# zulu_a7_4.net
KiCad netlist of a schematic drawn in Altium Designer
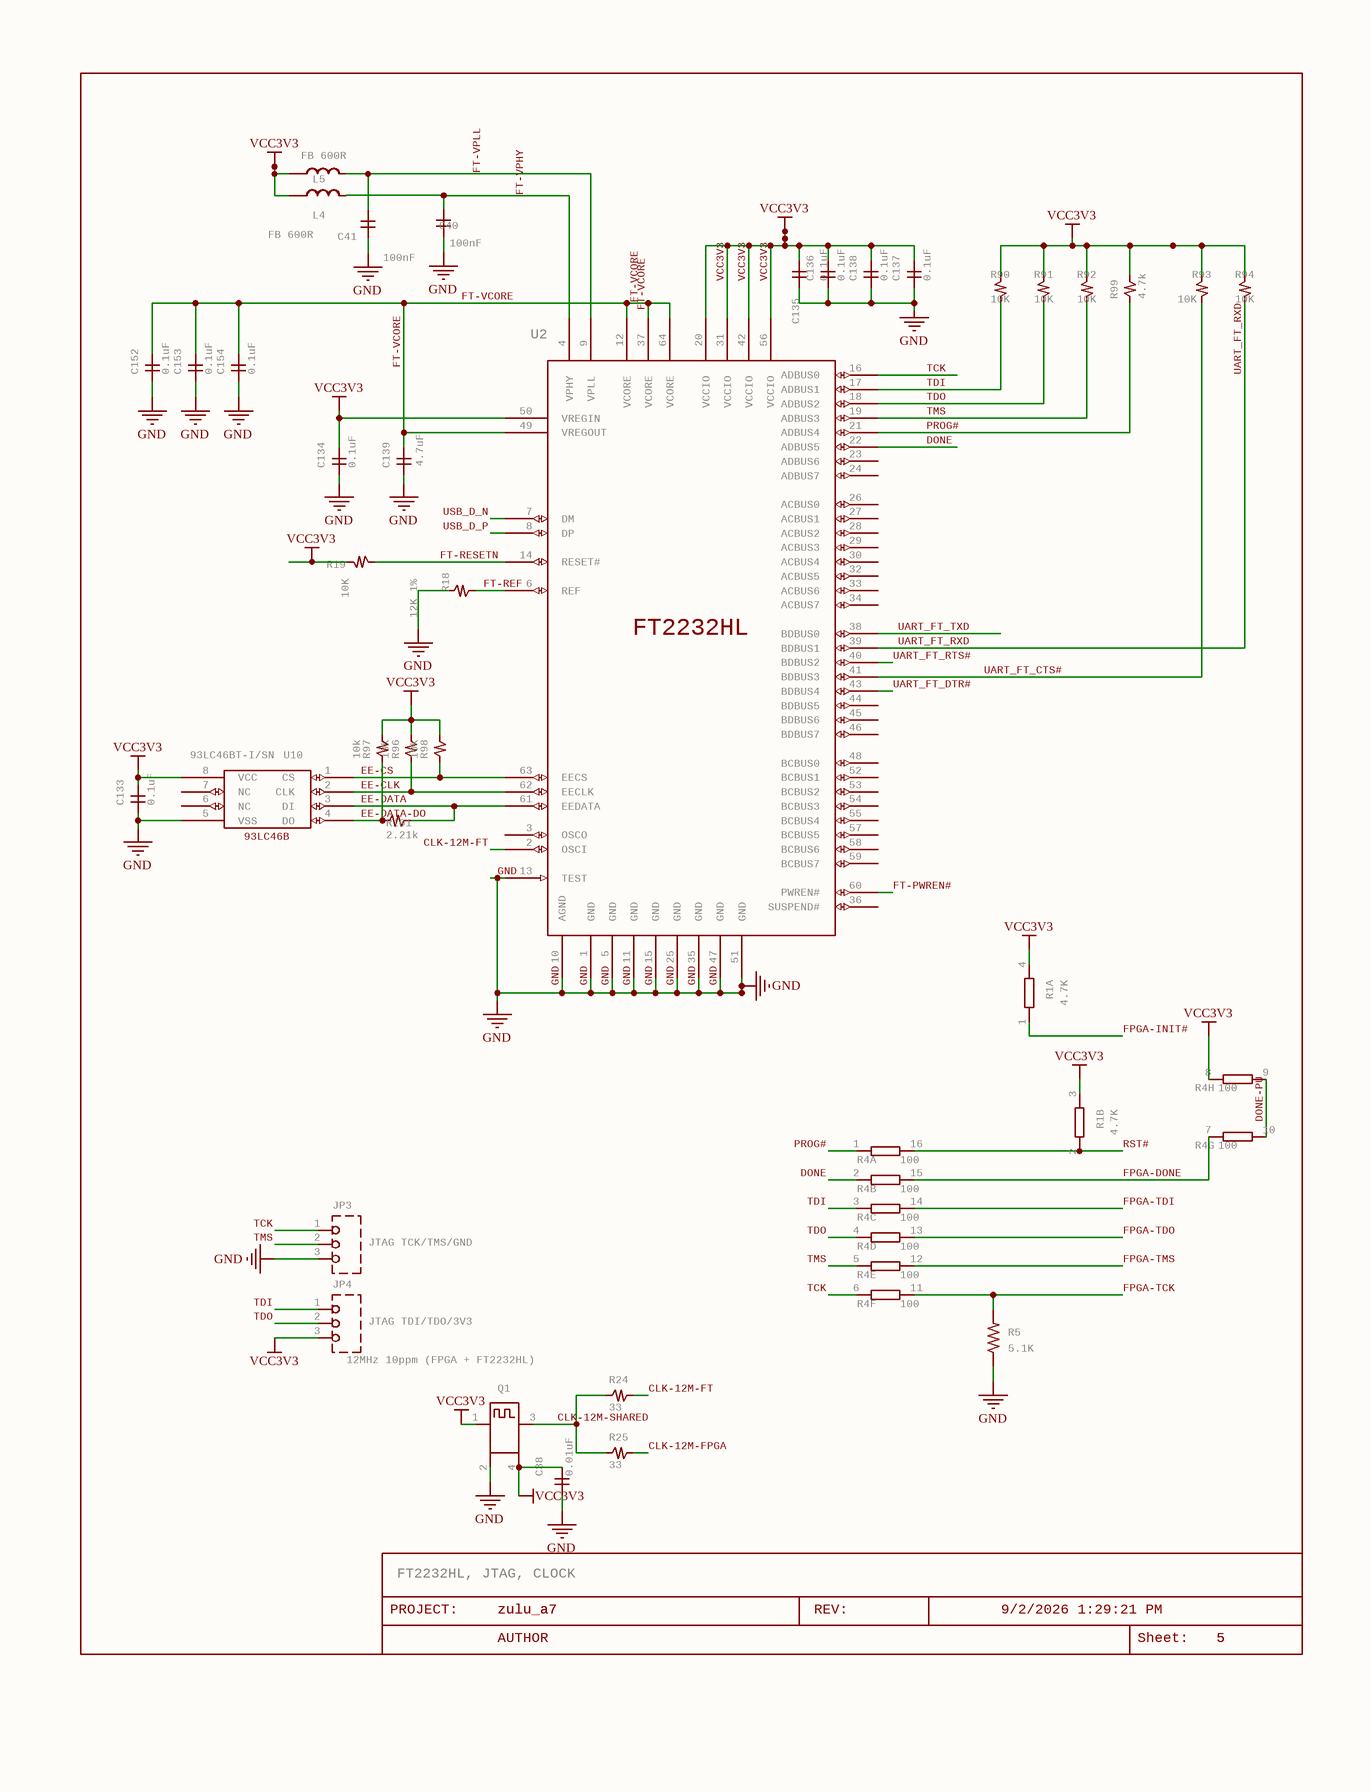
[diagram p0: zulu_a7_4.SchDoc]

(export (version "E")
  (design (tool "Eeschema 10.0.6"))
  (components
    (comp (ref "C38")
      (value "0.01uF")
      (footprint "C0201")
      (description "CAPACITOR, generic non-polarized, horizontal pins")
      (fields (field (name "MANF") "Murata"))
      (libsource (lib "rcl") (part "C-GENERICC0201"))
    )
    (comp (ref "C40")
      (value "100nF")
      (footprint "C0201")
      (description "CAPACITOR, generic non-polarized, horizontal pins")
      (fields (field (name "MANF") "Murata"))
      (libsource (lib "rcl") (part "C-GENERICC0201"))
    )
    (comp (ref "C41")
      (value "100nF")
      (footprint "C0201")
      (description "CAPACITOR, generic non-polarized, horizontal pins")
      (fields (field (name "MANF") "Murata"))
      (libsource (lib "") (part "C-GENERICC0201_2"))
    )
    (comp (ref "C133")
      (value "0.1uF")
      (footprint "C0201")
      (description "CAPACITOR, generic non-polarized, horizontal pins")
      (fields (field (name "MANF") "Murata"))
      (libsource (lib "rcl") (part "C-GENERICC0201"))
    )
    (comp (ref "C134")
      (value "0.1uF")
      (footprint "C0201")
      (description "CAPACITOR, generic non-polarized, horizontal pins")
      (fields (field (name "MANF") "Murata"))
      (libsource (lib "rcl") (part "C-GENERICC0201"))
    )
    (comp (ref "C135")
      (value "0.1uF")
      (footprint "C0201")
      (description "CAPACITOR, generic non-polarized, horizontal pins")
      (fields (field (name "MANF") "Murata"))
      (libsource (lib "rcl") (part "C-GENERICC0201"))
    )
    (comp (ref "C136")
      (value "0.1uF")
      (footprint "C0201")
      (description "CAPACITOR, generic non-polarized, horizontal pins")
      (fields (field (name "MANF") "Murata"))
      (libsource (lib "rcl") (part "C-GENERICC0201"))
    )
    (comp (ref "C137")
      (value "0.1uF")
      (footprint "C0201")
      (description "CAPACITOR, generic non-polarized, horizontal pins")
      (fields (field (name "MANF") "Murata"))
      (libsource (lib "rcl") (part "C-GENERICC0201"))
    )
    (comp (ref "C138")
      (value "0.1uF")
      (footprint "C0201")
      (description "CAPACITOR, generic non-polarized, horizontal pins")
      (fields (field (name "MANF") "Murata"))
      (libsource (lib "rcl") (part "C-GENERICC0201"))
    )
    (comp (ref "C139")
      (value "4.7uF")
      (footprint "C0402")
      (description "CAPACITOR, generic non-polarized, horizontal pins")
      (fields (field (name "MANF") "Taiyo Yuden"))
      (libsource (lib "rcl") (part "C-GENERICC0402"))
    )
    (comp (ref "C152")
      (value "0.1uF")
      (footprint "C0201")
      (description "CAPACITOR, generic non-polarized, horizontal pins")
      (fields (field (name "MANF") "Murata"))
      (libsource (lib "") (part "C-GENERICC0201_1"))
    )
    (comp (ref "C153")
      (value "0.1uF")
      (footprint "C0201")
      (description "CAPACITOR, generic non-polarized, horizontal pins")
      (fields (field (name "MANF") "Murata"))
      (libsource (lib "") (part "C-GENERICC0201_1"))
    )
    (comp (ref "C154")
      (value "0.1uF")
      (footprint "C0201")
      (description "CAPACITOR, generic non-polarized, horizontal pins")
      (fields (field (name "MANF") "Murata"))
      (libsource (lib "") (part "C-GENERICC0201_1"))
    )
    (comp (ref "FRAME4")
      (value "DOCFIELD")
      (description "DOCUMENT FIELD")
      (fields
        (field (name "LAST_DATE_TIME") "9/2/2026 1:29:21 PM")
        (field (name "SHEET") "Sheet:")
        (field (name "SHEET_1") "5")
        (field (name "REV") "REV:")
        (field (name "PROJECT") "PROJECT:")
        (field (name "DRAWING_NAME") "zulu_a7")
        (field (name "AUTHOR") "AUTHOR")
        (field (name "DRAWING_NAME_1") "zulu_a7")
        (field (name "SHEET_2") "5")
        (field (name "LIBRARYNAME") "ctambe")
      )
      (libsource (lib "ctambe") (part "DOCFIELD"))
    )
    (comp (ref "JP3")
      (value "JTAG TCK/TMS/GND")
      (footprint "1X03-NOSILK")
      (fields (field (name "LIBRARYNAME") "pinhead"))
      (libsource (lib "pinhead") (part "TESTPT-1X3NOSILK"))
    )
    (comp (ref "JP4")
      (value "JTAG TDI/TDO/3V3")
      (footprint "1X03-NOSILK")
      (fields (field (name "LIBRARYNAME") "pinhead"))
      (libsource (lib "pinhead") (part "TESTPT-1X3NOSILK"))
    )
    (comp (ref "L4")
      (value "FB 600R")
      (footprint "IND0603")
      (description "INDUCTOR, generic power inductor")
      (fields (field (name "MANF") "Murata") (field (name "LIBRARYNAME") "ctambe"))
      (libsource (lib "ctambe") (part "INDUCTOR"))
    )
    (comp (ref "L5")
      (value "FB 600R")
      (footprint "IND0603")
      (description "INDUCTOR, generic power inductor")
      (fields (field (name "MANF") "Murata") (field (name "LIBRARYNAME") "ctambe"))
      (libsource (lib "ctambe") (part "INDUCTOR"))
    )
    (comp (ref "Q1")
      (value "12MHz 10ppm (FPGA + FT2232HL)")
      (footprint "32X25")
      (description "Crystal Chip")
      (fields (field (name "MANF") "ECS") (field (name "LIBRARYNAME") "ctambe"))
      (libsource (lib "ctambe") (part "OSC_CHIPASEM1-12MHZ"))
    )
    (comp (ref "R1")
      (value "4.7K")
      (footprint "742C043")
      (description "Resistor 2-pack   Package of two resistors.")
      (fields (field (name "MANF") "CTS") (field (name "LIBRARYNAME") "ctambe"))
      (libsource (lib "") (part "RES2742_1"))
    )
    (comp (ref "R4")
      (value "100")
      (footprint "742C163")
      (description "Resistor 8-pack   Package of eight resistors, six used.")
      (fields (field (name "MANF") "CTS") (field (name "LIBRARYNAME") "ctambe"))
      (libsource (lib "ctambe") (part "RES8742"))
    )
    (comp (ref "R5")
      (value "5.1K")
      (footprint "R0201")
      (description "RESISTOR, American symbol")
      (fields (field (name "MANF") "Yageo"))
      (libsource (lib "rcl") (part "R-US_R0201"))
    )
    (comp (ref "R18")
      (value "12K 1%")
      (footprint "R0402")
      (description "RESISTOR, American symbol, small 2-zigzag variant (sheet 2 only)")
      (fields (field (name "MANF") "Yageo"))
      (libsource (lib "rcl") (part "R-US_SMALLR0402"))
    )
    (comp (ref "R19")
      (value "10K")
      (footprint "R0201")
      (description "RESISTOR, American symbol, small 2-zigzag variant (sheet 2 only)")
      (fields (field (name "MANF") "Yageo"))
      (libsource (lib "rcl") (part "R-US_SMALLR0201"))
    )
    (comp (ref "R24")
      (value "33")
      (footprint "R0201")
      (description "RESISTOR, American symbol, small 2-zigzag variant (sheet 2 only)")
      (fields (field (name "MANF") "Yageo"))
      (libsource (lib "rcl") (part "R-US_SMALLR0201"))
    )
    (comp (ref "R25")
      (value "33")
      (footprint "R0201")
      (description "RESISTOR, American symbol, small 2-zigzag variant (sheet 2 only)")
      (fields (field (name "MANF") "Yageo"))
      (libsource (lib "rcl") (part "R-US_SMALLR0201"))
    )
    (comp (ref "R90")
      (value "10K")
      (footprint "R0201")
      (description "RESISTOR, American symbol, small 2-zigzag variant (sheet 2 only)")
      (fields (field (name "MANF") "Yageo"))
      (libsource (lib "rcl") (part "R-US_SMALLR0201"))
    )
    (comp (ref "R91")
      (value "10K")
      (footprint "R0201")
      (description "RESISTOR, American symbol, small 2-zigzag variant (sheet 2 only)")
      (fields (field (name "MANF") "Yageo"))
      (libsource (lib "rcl") (part "R-US_SMALLR0201"))
    )
    (comp (ref "R92")
      (value "10K")
      (footprint "R0201")
      (description "RESISTOR, American symbol, small 2-zigzag variant (sheet 2 only)")
      (fields (field (name "MANF") "Yageo"))
      (libsource (lib "rcl") (part "R-US_SMALLR0201"))
    )
    (comp (ref "R93")
      (value "10K")
      (footprint "R0201")
      (description "RESISTOR, American symbol, small 2-zigzag variant (sheet 2 only)")
      (fields (field (name "MANF") "Yageo"))
      (libsource (lib "rcl") (part "R-US_SMALLR0201"))
    )
    (comp (ref "R94")
      (value "10K")
      (footprint "R0201")
      (description "RESISTOR, American symbol, small 2-zigzag variant (sheet 2 only)")
      (fields (field (name "MANF") "Yageo"))
      (libsource (lib "rcl") (part "R-US_SMALLR0201"))
    )
    (comp (ref "R96")
      (value "10k")
      (footprint "R0201")
      (description "RESISTOR, American symbol, small 2-zigzag variant (sheet 2 only)")
      (fields (field (name "MANF") "Yageo"))
      (libsource (lib "rcl") (part "R-US_SMALLR0201"))
    )
    (comp (ref "R97")
      (value "10k")
      (footprint "R0201")
      (description "RESISTOR, American symbol, small 2-zigzag variant (sheet 2 only)")
      (fields (field (name "MANF") "Yageo"))
      (libsource (lib "rcl") (part "R-US_SMALLR0201"))
    )
    (comp (ref "R98")
      (value "10k")
      (footprint "R0201")
      (description "RESISTOR, American symbol, small 2-zigzag variant (sheet 2 only)")
      (fields (field (name "MANF") "Yageo"))
      (libsource (lib "rcl") (part "R-US_SMALLR0201"))
    )
    (comp (ref "R99")
      (value "4.7k")
      (footprint "R0201")
      (description "RESISTOR, American symbol, small 2-zigzag variant (sheet 2 only)")
      (fields (field (name "MANF") "Yageo"))
      (libsource (lib "rcl") (part "R-US_SMALLR0201"))
    )
    (comp (ref "R101")
      (value "2.21k")
      (footprint "R0201")
      (description "RESISTOR, American symbol, small 2-zigzag variant (sheet 2 only)")
      (fields (field (name "MANF") "Yageo"))
      (libsource (lib "rcl") (part "R-US_SMALLR0201"))
    )
    (comp (ref "U2")
      (value "FT2232HL USB-UART/JTAG Bridge")
      (footprint "FT2232HL-LQFP64")
      (fields
        (field (name "FT2232HL") "FT2232HL")
        (field (name "MANF") "FTDI")
        (field (name "LIBRARYNAME") "ctambe")
      )
      (libsource (lib "ctambe") (part "FT2232HL-LQFP64"))
    )
    (comp (ref "U10")
      (value "93LC46BT-I/SN")
      (footprint "SPI-8_SOIC_150")
      (fields
        (field (name "93LC46B") "93LC46B")
        (field (name "MANF") "Microchip")
        (field (name "LIBRARYNAME") "ctambe")
      )
      (libsource (lib "ctambe") (part "EEPROM-93LC46B-I/SN"))
    )
  )
  (nets
    (net (code "1") (name "/CLK-12M-FPGA") (class "Default")
      (node (ref "R25") (pin "2") (pinfunction "2_2") (pintype "passive"))
    )
    (net (code "2") (name "/CLK-12M-FT") (class "Default")
      (node (ref "R24") (pin "2") (pinfunction "2_2") (pintype "passive"))
      (node (ref "U2") (pin "2") (pinfunction "OSCI_2") (pintype "bidirectional"))
    )
    (net (code "3") (name "/CLK-12M-SHARED") (class "Default")
      (node (ref "Q1") (pin "3") (pinfunction "3_3") (pintype "passive"))
      (node (ref "R24") (pin "1") (pinfunction "1_1") (pintype "passive"))
      (node (ref "R25") (pin "1") (pinfunction "1_1") (pintype "passive"))
    )
    (net (code "4") (name "/DONE") (class "Default")
      (node (ref "R4") (pin "2") (pinfunction "1_2") (pintype "passive"))
      (node (ref "U2") (pin "22") (pinfunction "ADBUS5_22") (pintype "bidirectional"))
    )
    (net (code "5") (name "/DONE-PU") (class "Default")
      (node (ref "R4") (pin "10") (pinfunction "2_10") (pintype "passive"))
      (node (ref "R4") (pin "9") (pinfunction "2_9") (pintype "passive"))
    )
    (net (code "6") (name "/EE-CLK") (class "Default")
      (node (ref "R96") (pin "1") (pinfunction "1_1") (pintype "passive"))
      (node (ref "U10") (pin "2") (pinfunction "CLK_2") (pintype "bidirectional"))
      (node (ref "U2") (pin "62") (pinfunction "EECLK_62") (pintype "bidirectional"))
    )
    (net (code "7") (name "/EE-CS") (class "Default")
      (node (ref "R98") (pin "1") (pinfunction "1_1") (pintype "passive"))
      (node (ref "U10") (pin "1") (pinfunction "CS_1") (pintype "bidirectional"))
      (node (ref "U2") (pin "63") (pinfunction "EECS_63") (pintype "bidirectional"))
    )
    (net (code "8") (name "/EE-DATA") (class "Default")
      (node (ref "R101") (pin "2") (pinfunction "2_2") (pintype "passive"))
      (node (ref "U10") (pin "3") (pinfunction "DI_3") (pintype "bidirectional"))
      (node (ref "U2") (pin "61") (pinfunction "EEDATA_61") (pintype "bidirectional"))
    )
    (net (code "9") (name "/EE-DATA-DO") (class "Default")
      (node (ref "R101") (pin "1") (pinfunction "1_1") (pintype "passive"))
      (node (ref "R97") (pin "1") (pinfunction "1_1") (pintype "passive"))
      (node (ref "U10") (pin "4") (pinfunction "DO_4") (pintype "bidirectional"))
    )
    (net (code "10") (name "/FPGA-DONE") (class "Default")
      (node (ref "R4") (pin "15") (pinfunction "2_15") (pintype "passive"))
      (node (ref "R4") (pin "7") (pinfunction "1_7") (pintype "passive"))
    )
    (net (code "11") (name "/FPGA-INIT#") (class "Default")
      (node (ref "R1") (pin "1") (pinfunction "1_1") (pintype "passive"))
    )
    (net (code "12") (name "/FPGA-TCK") (class "Default")
      (node (ref "R4") (pin "11") (pinfunction "2_11") (pintype "passive"))
      (node (ref "R5") (pin "2") (pinfunction "2_2") (pintype "passive"))
    )
    (net (code "13") (name "/FPGA-TDI") (class "Default")
      (node (ref "R4") (pin "14") (pinfunction "2_14") (pintype "passive"))
    )
    (net (code "14") (name "/FPGA-TDO") (class "Default")
      (node (ref "R4") (pin "13") (pinfunction "2_13") (pintype "passive"))
    )
    (net (code "15") (name "/FPGA-TMS") (class "Default")
      (node (ref "R4") (pin "12") (pinfunction "2_12") (pintype "passive"))
    )
    (net (code "16") (name "/FT-PWREN#") (class "Default")
      (node (ref "U2") (pin "60") (pinfunction "PWREN#_60") (pintype "bidirectional"))
    )
    (net (code "17") (name "/FT-REF") (class "Default")
      (node (ref "R18") (pin "2") (pinfunction "2_2") (pintype "passive"))
      (node (ref "U2") (pin "6") (pinfunction "REF_6") (pintype "bidirectional"))
    )
    (net (code "18") (name "/FT-RESETN") (class "Default")
      (node (ref "R19") (pin "1") (pinfunction "1_1") (pintype "passive"))
      (node (ref "U2") (pin "14") (pinfunction "RESET#_14") (pintype "bidirectional"))
    )
    (net (code "19") (name "/FT-VCORE") (class "Default")
      (node (ref "C139") (pin "2") (pinfunction "2_2") (pintype "passive"))
      (node (ref "C152") (pin "2") (pinfunction "2_2") (pintype "passive"))
      (node (ref "C153") (pin "2") (pinfunction "2_2") (pintype "passive"))
      (node (ref "C154") (pin "2") (pinfunction "2_2") (pintype "passive"))
      (node (ref "U2") (pin "12") (pinfunction "VCORE_12") (pintype "power_in"))
      (node (ref "U2") (pin "37") (pinfunction "VCORE_37") (pintype "power_in"))
      (node (ref "U2") (pin "49") (pinfunction "VREGOUT_49") (pintype "power_in"))
      (node (ref "U2") (pin "64") (pinfunction "VCORE_64") (pintype "power_in"))
    )
    (net (code "20") (name "/FT-VPHY") (class "Default")
      (node (ref "C40") (pin "2") (pinfunction "2_2") (pintype "passive"))
      (node (ref "L4") (pin "1") (pinfunction "1_1") (pintype "passive"))
      (node (ref "U2") (pin "4") (pinfunction "VPHY_4") (pintype "power_in"))
    )
    (net (code "21") (name "/FT-VPLL") (class "Default")
      (node (ref "C41") (pin "2") (pinfunction "2_2") (pintype "passive"))
      (node (ref "L5") (pin "1") (pinfunction "1_1") (pintype "passive"))
      (node (ref "U2") (pin "9") (pinfunction "VPLL_9") (pintype "power_in"))
    )
    (net (code "22") (name "/PROG#") (class "Default")
      (node (ref "R4") (pin "1") (pinfunction "1_1") (pintype "passive"))
      (node (ref "R99") (pin "1") (pinfunction "1_1") (pintype "passive"))
      (node (ref "U2") (pin "21") (pinfunction "ADBUS4_21") (pintype "bidirectional"))
    )
    (net (code "23") (name "/RST#") (class "Default")
      (node (ref "R1") (pin "2") (pinfunction "1_2") (pintype "passive"))
      (node (ref "R4") (pin "16") (pinfunction "2_16") (pintype "passive"))
    )
    (net (code "24") (name "/TCK") (class "Default")
      (node (ref "JP3") (pin "1") (pinfunction "1_1") (pintype "passive"))
      (node (ref "R4") (pin "6") (pinfunction "1_6") (pintype "passive"))
      (node (ref "U2") (pin "16") (pinfunction "ADBUS0_16") (pintype "bidirectional"))
    )
    (net (code "25") (name "/TDI") (class "Default")
      (node (ref "JP4") (pin "1") (pinfunction "1_1") (pintype "passive"))
      (node (ref "R4") (pin "3") (pinfunction "1_3") (pintype "passive"))
      (node (ref "R90") (pin "1") (pinfunction "1_1") (pintype "passive"))
      (node (ref "U2") (pin "17") (pinfunction "ADBUS1_17") (pintype "bidirectional"))
    )
    (net (code "26") (name "/TDO") (class "Default")
      (node (ref "JP4") (pin "2") (pinfunction "2_2") (pintype "passive"))
      (node (ref "R4") (pin "4") (pinfunction "1_4") (pintype "passive"))
      (node (ref "R91") (pin "1") (pinfunction "1_1") (pintype "passive"))
      (node (ref "U2") (pin "18") (pinfunction "ADBUS2_18") (pintype "bidirectional"))
    )
    (net (code "27") (name "/TMS") (class "Default")
      (node (ref "JP3") (pin "2") (pinfunction "2_2") (pintype "passive"))
      (node (ref "R4") (pin "5") (pinfunction "1_5") (pintype "passive"))
      (node (ref "R92") (pin "1") (pinfunction "1_1") (pintype "passive"))
      (node (ref "U2") (pin "19") (pinfunction "ADBUS3_19") (pintype "bidirectional"))
    )
    (net (code "28") (name "/UART_FT_CTS#") (class "Default")
      (node (ref "R93") (pin "1") (pinfunction "1_1") (pintype "passive"))
      (node (ref "U2") (pin "41") (pinfunction "BDBUS3_41") (pintype "bidirectional"))
    )
    (net (code "29") (name "/UART_FT_DTR#") (class "Default")
      (node (ref "U2") (pin "43") (pinfunction "BDBUS4_43") (pintype "bidirectional"))
    )
    (net (code "30") (name "/UART_FT_RTS#") (class "Default")
      (node (ref "U2") (pin "40") (pinfunction "BDBUS2_40") (pintype "bidirectional"))
    )
    (net (code "31") (name "/UART_FT_RXD") (class "Default")
      (node (ref "R94") (pin "1") (pinfunction "1_1") (pintype "passive"))
      (node (ref "U2") (pin "39") (pinfunction "BDBUS1_39") (pintype "bidirectional"))
    )
    (net (code "32") (name "/UART_FT_TXD") (class "Default")
      (node (ref "U2") (pin "38") (pinfunction "BDBUS0_38") (pintype "bidirectional"))
    )
    (net (code "33") (name "/USB_D_N") (class "Default")
      (node (ref "U2") (pin "7") (pinfunction "DM_7") (pintype "bidirectional"))
    )
    (net (code "34") (name "/USB_D_P") (class "Default")
      (node (ref "U2") (pin "8") (pinfunction "DP_8") (pintype "bidirectional"))
    )
    (net (code "35") (name "GND") (class "Default")
      (node (ref "C133") (pin "1") (pinfunction "1_1") (pintype "passive"))
      (node (ref "C134") (pin "1") (pinfunction "1_1") (pintype "passive"))
      (node (ref "C135") (pin "1") (pinfunction "1_1") (pintype "passive"))
      (node (ref "C136") (pin "1") (pinfunction "1_1") (pintype "passive"))
      (node (ref "C137") (pin "1") (pinfunction "1_1") (pintype "passive"))
      (node (ref "C138") (pin "1") (pinfunction "1_1") (pintype "passive"))
      (node (ref "C139") (pin "1") (pinfunction "1_1") (pintype "passive"))
      (node (ref "C152") (pin "1") (pinfunction "1_1") (pintype "passive"))
      (node (ref "C153") (pin "1") (pinfunction "1_1") (pintype "passive"))
      (node (ref "C154") (pin "1") (pinfunction "1_1") (pintype "passive"))
      (node (ref "C38") (pin "1") (pinfunction "1_1") (pintype "passive"))
      (node (ref "C40") (pin "1") (pinfunction "1_1") (pintype "passive"))
      (node (ref "C41") (pin "1") (pinfunction "1_1") (pintype "passive"))
      (node (ref "JP3") (pin "3") (pinfunction "3_3") (pintype "passive"))
      (node (ref "Q1") (pin "2") (pinfunction "2_2") (pintype "passive"))
      (node (ref "R18") (pin "1") (pinfunction "1_1") (pintype "passive"))
      (node (ref "R5") (pin "1") (pinfunction "1_1") (pintype "passive"))
      (node (ref "U10") (pin "5") (pinfunction "VSS_5") (pintype "power_in"))
      (node (ref "U2") (pin "1") (pinfunction "GND_1") (pintype "power_in"))
      (node (ref "U2") (pin "10") (pinfunction "AGND_10") (pintype "power_in"))
      (node (ref "U2") (pin "11") (pinfunction "GND_11") (pintype "power_in"))
      (node (ref "U2") (pin "13") (pinfunction "TEST_13") (pintype "input"))
      (node (ref "U2") (pin "15") (pinfunction "GND_15") (pintype "power_in"))
      (node (ref "U2") (pin "25") (pinfunction "GND_25") (pintype "power_in"))
      (node (ref "U2") (pin "35") (pinfunction "GND_35") (pintype "power_in"))
      (node (ref "U2") (pin "47") (pinfunction "GND_47") (pintype "power_in"))
      (node (ref "U2") (pin "5") (pinfunction "GND_5") (pintype "power_in"))
      (node (ref "U2") (pin "51") (pinfunction "GND_51") (pintype "power_in"))
    )
    (net (code "36") (name "VCC3V3") (class "Default")
      (node (ref "C133") (pin "2") (pinfunction "2_2") (pintype "passive"))
      (node (ref "C134") (pin "2") (pinfunction "2_2") (pintype "passive"))
      (node (ref "C135") (pin "2") (pinfunction "2_2") (pintype "passive"))
      (node (ref "C136") (pin "2") (pinfunction "2_2") (pintype "passive"))
      (node (ref "C137") (pin "2") (pinfunction "2_2") (pintype "passive"))
      (node (ref "C138") (pin "2") (pinfunction "2_2") (pintype "passive"))
      (node (ref "C38") (pin "2") (pinfunction "2_2") (pintype "passive"))
      (node (ref "JP4") (pin "3") (pinfunction "3_3") (pintype "passive"))
      (node (ref "L4") (pin "2") (pinfunction "2_2") (pintype "passive"))
      (node (ref "L5") (pin "2") (pinfunction "2_2") (pintype "passive"))
      (node (ref "Q1") (pin "1") (pinfunction "1_1") (pintype "passive"))
      (node (ref "Q1") (pin "4") (pinfunction "4_4") (pintype "passive"))
      (node (ref "R1") (pin "3") (pinfunction "2_3") (pintype "passive"))
      (node (ref "R1") (pin "4") (pinfunction "2_4") (pintype "passive"))
      (node (ref "R19") (pin "2") (pinfunction "2_2") (pintype "passive"))
      (node (ref "R4") (pin "8") (pinfunction "1_8") (pintype "passive"))
      (node (ref "R90") (pin "2") (pinfunction "2_2") (pintype "passive"))
      (node (ref "R91") (pin "2") (pinfunction "2_2") (pintype "passive"))
      (node (ref "R92") (pin "2") (pinfunction "2_2") (pintype "passive"))
      (node (ref "R93") (pin "2") (pinfunction "2_2") (pintype "passive"))
      (node (ref "R94") (pin "2") (pinfunction "2_2") (pintype "passive"))
      (node (ref "R96") (pin "2") (pinfunction "2_2") (pintype "passive"))
      (node (ref "R97") (pin "2") (pinfunction "2_2") (pintype "passive"))
      (node (ref "R98") (pin "2") (pinfunction "2_2") (pintype "passive"))
      (node (ref "R99") (pin "2") (pinfunction "2_2") (pintype "passive"))
      (node (ref "U10") (pin "8") (pinfunction "VCC_8") (pintype "power_in"))
      (node (ref "U2") (pin "20") (pinfunction "VCCIO_20") (pintype "power_in"))
      (node (ref "U2") (pin "31") (pinfunction "VCCIO_31") (pintype "power_in"))
      (node (ref "U2") (pin "42") (pinfunction "VCCIO_42") (pintype "power_in"))
      (node (ref "U2") (pin "50") (pinfunction "VREGIN_50") (pintype "power_in"))
      (node (ref "U2") (pin "56") (pinfunction "VCCIO_56") (pintype "power_in"))
    )
    (net (code "37") (name "unconnected-(U2-ACBUS0-Pad26)") (class "Default")
      (node (ref "U2") (pin "26") (pinfunction "ACBUS0_26") (pintype "bidirectional"))
    )
    (net (code "38") (name "unconnected-(U2-ACBUS1-Pad27)") (class "Default")
      (node (ref "U2") (pin "27") (pinfunction "ACBUS1_27") (pintype "bidirectional"))
    )
    (net (code "39") (name "unconnected-(U2-ACBUS2-Pad28)") (class "Default")
      (node (ref "U2") (pin "28") (pinfunction "ACBUS2_28") (pintype "bidirectional"))
    )
    (net (code "40") (name "unconnected-(U2-ACBUS3-Pad29)") (class "Default")
      (node (ref "U2") (pin "29") (pinfunction "ACBUS3_29") (pintype "bidirectional"))
    )
    (net (code "41") (name "unconnected-(U2-ACBUS4-Pad30)") (class "Default")
      (node (ref "U2") (pin "30") (pinfunction "ACBUS4_30") (pintype "bidirectional"))
    )
    (net (code "42") (name "unconnected-(U2-ACBUS5-Pad32)") (class "Default")
      (node (ref "U2") (pin "32") (pinfunction "ACBUS5_32") (pintype "bidirectional"))
    )
    (net (code "43") (name "unconnected-(U2-ACBUS6-Pad33)") (class "Default")
      (node (ref "U2") (pin "33") (pinfunction "ACBUS6_33") (pintype "bidirectional"))
    )
    (net (code "44") (name "unconnected-(U2-ACBUS7-Pad34)") (class "Default")
      (node (ref "U2") (pin "34") (pinfunction "ACBUS7_34") (pintype "bidirectional"))
    )
    (net (code "45") (name "unconnected-(U2-ADBUS6-Pad23)") (class "Default")
      (node (ref "U2") (pin "23") (pinfunction "ADBUS6_23") (pintype "bidirectional"))
    )
    (net (code "46") (name "unconnected-(U2-ADBUS7-Pad24)") (class "Default")
      (node (ref "U2") (pin "24") (pinfunction "ADBUS7_24") (pintype "bidirectional"))
    )
    (net (code "47") (name "unconnected-(U2-BCBUS0-Pad48)") (class "Default")
      (node (ref "U2") (pin "48") (pinfunction "BCBUS0_48") (pintype "bidirectional"))
    )
    (net (code "48") (name "unconnected-(U2-BCBUS1-Pad52)") (class "Default")
      (node (ref "U2") (pin "52") (pinfunction "BCBUS1_52") (pintype "bidirectional"))
    )
    (net (code "49") (name "unconnected-(U2-BCBUS2-Pad53)") (class "Default")
      (node (ref "U2") (pin "53") (pinfunction "BCBUS2_53") (pintype "bidirectional"))
    )
    (net (code "50") (name "unconnected-(U2-BCBUS3-Pad54)") (class "Default")
      (node (ref "U2") (pin "54") (pinfunction "BCBUS3_54") (pintype "bidirectional"))
    )
    (net (code "51") (name "unconnected-(U2-BCBUS4-Pad55)") (class "Default")
      (node (ref "U2") (pin "55") (pinfunction "BCBUS4_55") (pintype "bidirectional"))
    )
    (net (code "52") (name "unconnected-(U2-BCBUS5-Pad57)") (class "Default")
      (node (ref "U2") (pin "57") (pinfunction "BCBUS5_57") (pintype "bidirectional"))
    )
    (net (code "53") (name "unconnected-(U2-BCBUS6-Pad58)") (class "Default")
      (node (ref "U2") (pin "58") (pinfunction "BCBUS6_58") (pintype "bidirectional"))
    )
    (net (code "54") (name "unconnected-(U2-BCBUS7-Pad59)") (class "Default")
      (node (ref "U2") (pin "59") (pinfunction "BCBUS7_59") (pintype "bidirectional"))
    )
    (net (code "55") (name "unconnected-(U2-BDBUS5-Pad44)") (class "Default")
      (node (ref "U2") (pin "44") (pinfunction "BDBUS5_44") (pintype "bidirectional"))
    )
    (net (code "56") (name "unconnected-(U2-BDBUS6-Pad45)") (class "Default")
      (node (ref "U2") (pin "45") (pinfunction "BDBUS6_45") (pintype "bidirectional"))
    )
    (net (code "57") (name "unconnected-(U2-BDBUS7-Pad46)") (class "Default")
      (node (ref "U2") (pin "46") (pinfunction "BDBUS7_46") (pintype "bidirectional"))
    )
    (net (code "58") (name "unconnected-(U2-OSCO-Pad3)") (class "Default")
      (node (ref "U2") (pin "3") (pinfunction "OSCO_3") (pintype "bidirectional"))
    )
    (net (code "59") (name "unconnected-(U2-SUSPEND#-Pad36)") (class "Default")
      (node (ref "U2") (pin "36") (pinfunction "SUSPEND#_36") (pintype "bidirectional"))
    )
    (net (code "60") (name "unconnected-(U10-NC-Pad6)") (class "Default")
      (node (ref "U10") (pin "6") (pinfunction "NC_6") (pintype "bidirectional"))
    )
    (net (code "61") (name "unconnected-(U10-NC-Pad7)") (class "Default")
      (node (ref "U10") (pin "7") (pinfunction "NC_7") (pintype "bidirectional"))
    )
  )
)
